# TSL2591.net
KiCad netlist of a schematic drawn in Altium Designer
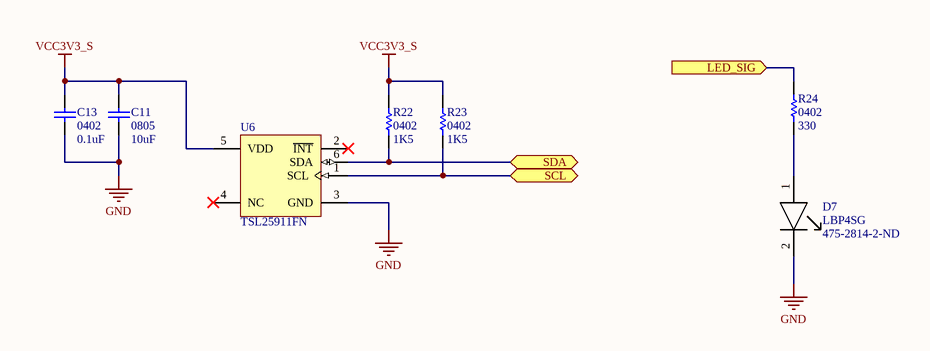
[diagram p0: TSL2591.SchDoc]

(export (version "E")
  (design (tool "Eeschema 10.0.6"))
  (components
    (comp (ref "C11")
      (value "0805")
      (footprint "CAP0805R")
      (description "Capacitor")
      (fields
        (field (name "ALTIUM_VALUE") "10uF")
        (field (name "MANUFACTURER") "TDK")
        (field (name "MANUFACTURER PART NUMBER") "CGA4J1X7R0J106K125AC")
        (field (name "PUBLISHER") "Altium Limited")
      )
      (libsource (lib "Miscellaneous Devices") (part "Cap"))
    )
    (comp (ref "C13")
      (value "0402")
      (footprint "CAP0402R")
      (description "Capacitor")
      (fields
        (field (name "ALTIUM_VALUE") "0.1uF")
        (field (name "MANUFACTURER") "Murata")
        (field (name "MANUFACTURER PART NUMBER") "GCM155R71C104KA55J")
        (field (name "PUBLISHER") "Altium Limited")
      )
      (libsource (lib "Miscellaneous Devices") (part "Cap"))
    )
    (comp (ref "D7")
      (value "LBP4SG")
      (footprint "LB P4SG")
      (description "LED BLUE CLEAR SMD BOTTOM ENTRY")
      (fields (field (name "SUPPLIER PART NUMBER 1") "475-2814-2-ND"))
      (libsource (lib "heron-general") (part "LB P4SG"))
    )
    (comp (ref "R22")
      (value "0402")
      (footprint "RES0402R")
      (description "Resistor")
      (fields (field (name "ALTIUM_VALUE") "1K5") (field (name "PUBLISHER") "Altium Limited"))
      (libsource (lib "Miscellaneous Devices") (part "Res1"))
    )
    (comp (ref "R23")
      (value "0402")
      (footprint "RES0402R")
      (description "Resistor")
      (fields (field (name "ALTIUM_VALUE") "1K5") (field (name "PUBLISHER") "Altium Limited"))
      (libsource (lib "Miscellaneous Devices") (part "Res1"))
    )
    (comp (ref "R24")
      (value "0402")
      (footprint "RES0402R")
      (description "Resistor")
      (fields (field (name "ALTIUM_VALUE") "330") (field (name "PUBLISHER") "Altium Limited"))
      (libsource (lib "Miscellaneous Devices") (part "Res1"))
    )
    (comp (ref "U6")
      (value "TSL25911FN")
      (footprint "AMS-FN-6-2400X2000DE_V")
      (description "Light-to-Digital Converter with I2C Interface, 2.7 to 3.6 V, -30 to 70 degC, FN-6, Pb-Free, Reel")
      (fields (field (name "MANUFACTURER") "AMS"))
      (libsource (lib "PAY") (part "TSL25911FN"))
    )
  )
  (nets
    (net (code "1") (name "/LED_SIG") (class "Default")
      (node (ref "R24") (pin "1") (pinfunction "1_1") (pintype "passive"))
    )
    (net (code "2") (name "/SCL") (class "Default")
      (node (ref "R23") (pin "1") (pinfunction "1_1") (pintype "passive"))
      (node (ref "U6") (pin "1") (pinfunction "SCL_1") (pintype "input"))
    )
    (net (code "3") (name "/SDA") (class "Default")
      (node (ref "R22") (pin "1") (pinfunction "1_1") (pintype "passive"))
      (node (ref "U6") (pin "6") (pinfunction "SDA_6") (pintype "bidirectional"))
    )
    (net (code "4") (name "GND") (class "Default")
      (node (ref "C11") (pin "1") (pinfunction "1_1") (pintype "passive"))
      (node (ref "C13") (pin "1") (pinfunction "1_1") (pintype "passive"))
      (node (ref "D7") (pin "2") (pinfunction "Cathode_2") (pintype "passive"))
      (node (ref "U6") (pin "3") (pinfunction "GND_3") (pintype "power_in"))
    )
    (net (code "5") (name "Net-(D7-Anode)") (class "Default")
      (node (ref "D7") (pin "1") (pinfunction "Anode_1") (pintype "passive"))
      (node (ref "R24") (pin "2") (pinfunction "2_2") (pintype "passive"))
    )
    (net (code "6") (name "VCC3V3_S") (class "Default")
      (node (ref "C11") (pin "2") (pinfunction "2_2") (pintype "passive"))
      (node (ref "C13") (pin "2") (pinfunction "2_2") (pintype "passive"))
      (node (ref "R22") (pin "2") (pinfunction "2_2") (pintype "passive"))
      (node (ref "R23") (pin "2") (pinfunction "2_2") (pintype "passive"))
      (node (ref "U6") (pin "5") (pinfunction "VDD_5") (pintype "power_in"))
    )
    (net (code "7") (name "unconnected-(U6-NC-Pad4)") (class "Default")
      (node (ref "U6") (pin "4") (pinfunction "NC_4") (pintype "passive+no_connect"))
    )
    (net (code "8") (name "unconnected-(U6-~{INT}-Pad2)") (class "Default")
      (node (ref "U6") (pin "2") (pinfunction "~{INT}_2") (pintype "open_collector+no_connect"))
    )
  )
)
